# alu.net
KiCad netlist of a schematic drawn in EAGLE
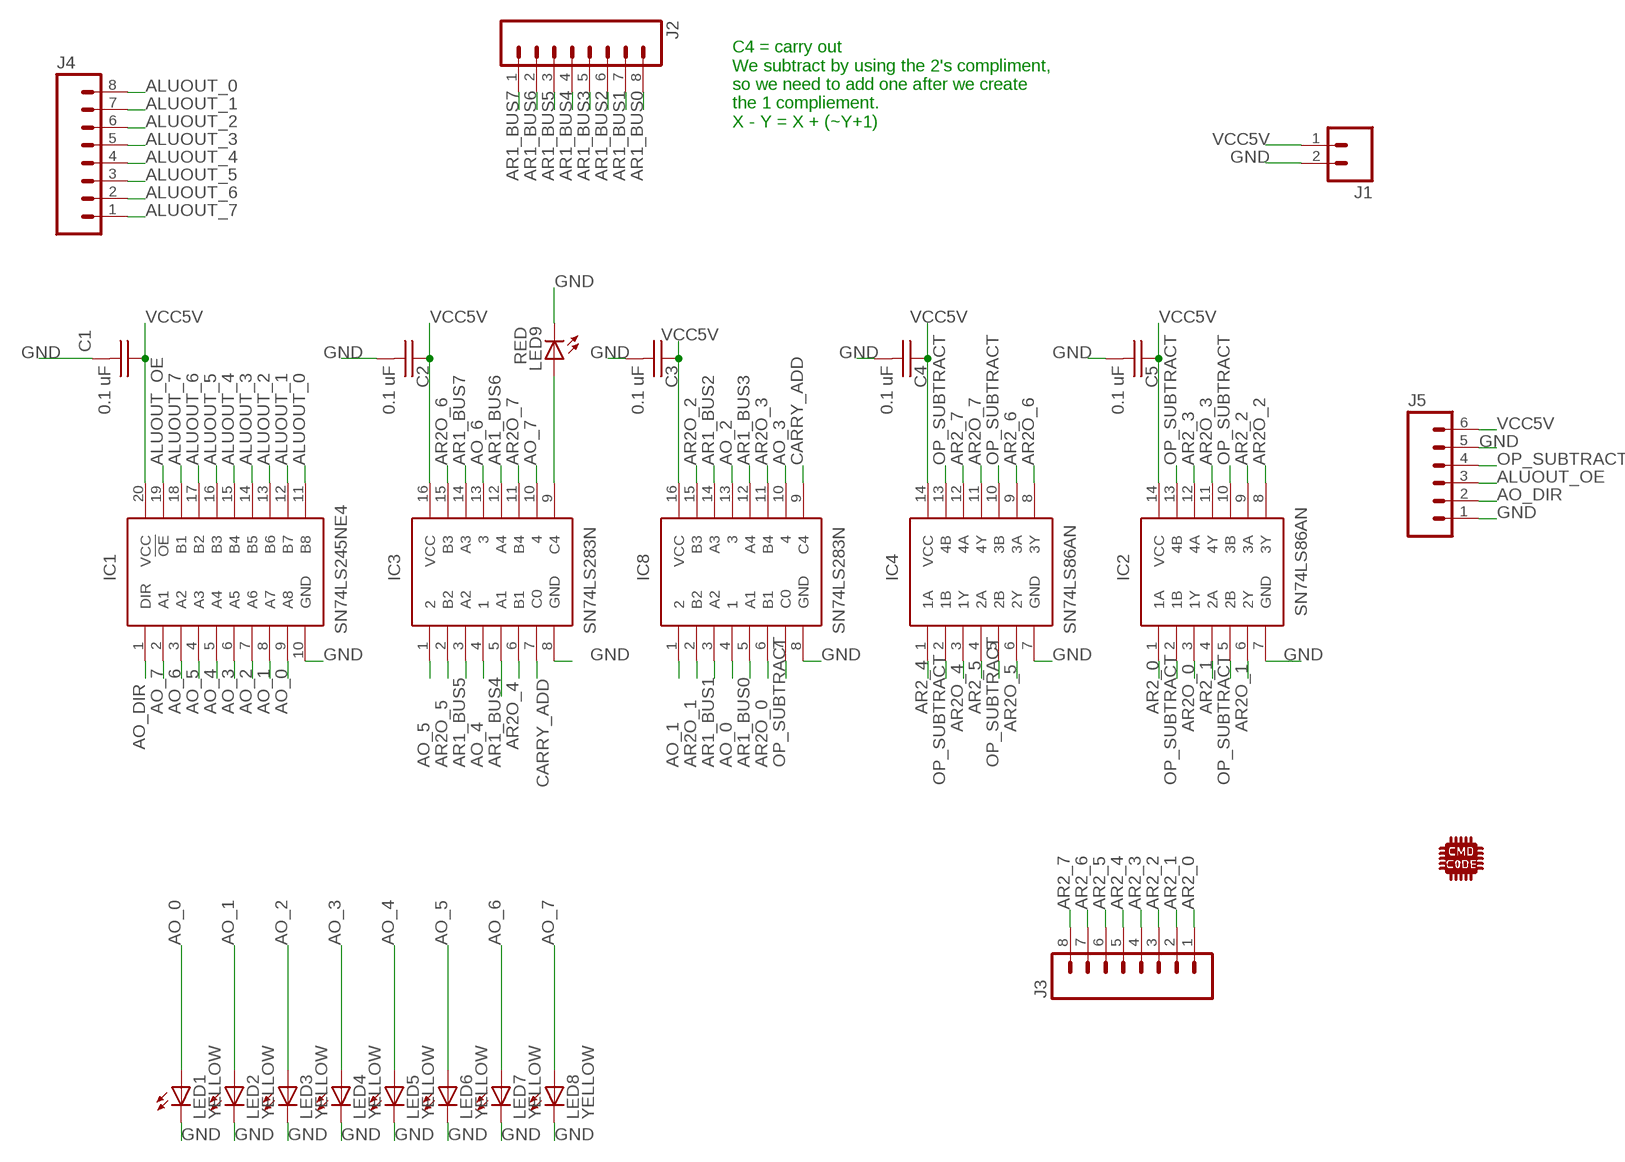
[diagram p0: schematic, sheet 1]

(export (version "E")
  (design (tool "Eeschema 10.0.6"))
  (components
    (comp (ref "C1")
      (value "0.1 uF")
      (footprint "eagle-import:C050-025X075")
      (libsource (lib "eagle-import") (part "C-US050-025X075"))
    )
    (comp (ref "C2")
      (value "0.1 uF")
      (footprint "eagle-import:C050-025X075")
      (libsource (lib "eagle-import") (part "C-US050-025X075"))
    )
    (comp (ref "C3")
      (value "0.1 uF")
      (footprint "eagle-import:C050-025X075")
      (libsource (lib "eagle-import") (part "C-US050-025X075"))
    )
    (comp (ref "C4")
      (value "0.1 uF")
      (footprint "eagle-import:C050-025X075")
      (libsource (lib "eagle-import") (part "C-US050-025X075"))
    )
    (comp (ref "C5")
      (value "0.1 uF")
      (footprint "eagle-import:C050-025X075")
      (libsource (lib "eagle-import") (part "C-US050-025X075"))
    )
    (comp (ref "IC1")
      (value "SN74LS245NE4")
      (footprint "eagle-import:DIP794W53P254L2540H508Q20N")
      (fields (field (name "MOUSER_PART_NUMBER") "595-SN74LS245NE4"))
      (libsource (lib "eagle-import") (part "SN74LS245NE4"))
    )
    (comp (ref "IC2")
      (value "SN74LS86AN")
      (footprint "eagle-import:DIP254P762X508-14")
      (fields (field (name "MOUSER_PART_NUMBER") "595-SN74LS86AN") (field (name "RS_PART_NUMBER") "3686641"))
      (libsource (lib "eagle-import") (part "SN74LS86AN"))
    )
    (comp (ref "IC3")
      (value "SN74LS283N")
      (footprint "eagle-import:DIP254P762X508-16")
      (fields (field (name "MOUSER_PART_NUMBER") "595-SN74LS283N") (field (name "RS_PART_NUMBER") "0309212"))
      (libsource (lib "eagle-import") (part "SN74LS283N"))
    )
    (comp (ref "IC4")
      (value "SN74LS86AN")
      (footprint "eagle-import:DIP254P762X508-14")
      (fields (field (name "MOUSER_PART_NUMBER") "595-SN74LS86AN") (field (name "RS_PART_NUMBER") "3686641"))
      (libsource (lib "eagle-import") (part "SN74LS86AN"))
    )
    (comp (ref "IC8")
      (value "SN74LS283N")
      (footprint "eagle-import:DIP254P762X508-16")
      (fields (field (name "MOUSER_PART_NUMBER") "595-SN74LS283N") (field (name "RS_PART_NUMBER") "0309212"))
      (libsource (lib "eagle-import") (part "SN74LS283N"))
    )
    (comp (ref "J1")
      (value "M02PTH")
      (footprint "eagle-import:1X02")
      (libsource (lib "eagle-import") (part "M02PTH"))
    )
    (comp (ref "J2")
      (value "M08SILK_FEMALE_PTH")
      (footprint "eagle-import:1X08")
      (libsource (lib "eagle-import") (part "M08SILK_FEMALE_PTH"))
    )
    (comp (ref "J3")
      (value "M08SILK_FEMALE_PTH")
      (footprint "eagle-import:1X08")
      (libsource (lib "eagle-import") (part "M08SILK_FEMALE_PTH"))
    )
    (comp (ref "J4")
      (value "M08SILK_FEMALE_PTH")
      (footprint "eagle-import:1X08")
      (libsource (lib "eagle-import") (part "M08SILK_FEMALE_PTH"))
    )
    (comp (ref "J5")
      (value "M06SILK_FEMALE_PTH")
      (footprint "eagle-import:1X06")
      (libsource (lib "eagle-import") (part "M06SILK_FEMALE_PTH"))
    )
    (comp (ref "LED1")
      (value "YELLOW")
      (footprint "eagle-import:LED3MM-NS")
      (libsource (lib "eagle-import") (part "LED-3MM-NO_SILK"))
    )
    (comp (ref "LED2")
      (value "YELLOW")
      (footprint "eagle-import:LED3MM-NS")
      (libsource (lib "eagle-import") (part "LED-3MM-NO_SILK"))
    )
    (comp (ref "LED3")
      (value "YELLOW")
      (footprint "eagle-import:LED3MM-NS")
      (libsource (lib "eagle-import") (part "LED-3MM-NO_SILK"))
    )
    (comp (ref "LED4")
      (value "YELLOW")
      (footprint "eagle-import:LED3MM-NS")
      (libsource (lib "eagle-import") (part "LED-3MM-NO_SILK"))
    )
    (comp (ref "LED5")
      (value "YELLOW")
      (footprint "eagle-import:LED3MM-NS")
      (libsource (lib "eagle-import") (part "LED-3MM-NO_SILK"))
    )
    (comp (ref "LED6")
      (value "YELLOW")
      (footprint "eagle-import:LED3MM-NS")
      (libsource (lib "eagle-import") (part "LED-3MM-NO_SILK"))
    )
    (comp (ref "LED7")
      (value "YELLOW")
      (footprint "eagle-import:LED3MM-NS")
      (libsource (lib "eagle-import") (part "LED-3MM-NO_SILK"))
    )
    (comp (ref "LED8")
      (value "YELLOW")
      (footprint "eagle-import:LED3MM-NS")
      (libsource (lib "eagle-import") (part "LED-3MM-NO_SILK"))
    )
    (comp (ref "LED9")
      (value "RED")
      (footprint "eagle-import:LED3MM-NS")
      (libsource (lib "eagle-import") (part "LED-3MM-NO_SILK"))
    )
    (comp (ref "U$1")
      (value "CMD_C0DE_LOGOCMD_CODE_LOGO_TOP_COPPER")
      (footprint "eagle-import:CMD_C0DE_LOGO_TOP_COPPER")
      (libsource (lib "eagle-import") (part "CMD_C0DE_LOGOCMD_CODE_LOGO_TOP_COPPER"))
    )
  )
  (nets
    (net (code "1") (name "/ALUOUT_0") (class "Default")
      (node (ref "IC1") (pin "11") (pinfunction "B8_11") (pintype "bidirectional"))
      (node (ref "J4") (pin "8") (pinfunction "8_8") (pintype "passive"))
    )
    (net (code "2") (name "/ALUOUT_1") (class "Default")
      (node (ref "IC1") (pin "12") (pinfunction "B7_12") (pintype "bidirectional"))
      (node (ref "J4") (pin "7") (pinfunction "7_7") (pintype "passive"))
    )
    (net (code "3") (name "/ALUOUT_2") (class "Default")
      (node (ref "IC1") (pin "13") (pinfunction "B6_13") (pintype "bidirectional"))
      (node (ref "J4") (pin "6") (pinfunction "6_6") (pintype "passive"))
    )
    (net (code "4") (name "/ALUOUT_3") (class "Default")
      (node (ref "IC1") (pin "14") (pinfunction "B5_14") (pintype "bidirectional"))
      (node (ref "J4") (pin "5") (pinfunction "5_5") (pintype "passive"))
    )
    (net (code "5") (name "/ALUOUT_4") (class "Default")
      (node (ref "IC1") (pin "15") (pinfunction "B4_15") (pintype "bidirectional"))
      (node (ref "J4") (pin "4") (pinfunction "4_4") (pintype "passive"))
    )
    (net (code "6") (name "/ALUOUT_5") (class "Default")
      (node (ref "IC1") (pin "16") (pinfunction "B3_16") (pintype "bidirectional"))
      (node (ref "J4") (pin "3") (pinfunction "3_3") (pintype "passive"))
    )
    (net (code "7") (name "/ALUOUT_6") (class "Default")
      (node (ref "IC1") (pin "17") (pinfunction "B2_17") (pintype "bidirectional"))
      (node (ref "J4") (pin "2") (pinfunction "2_2") (pintype "passive"))
    )
    (net (code "8") (name "/ALUOUT_7") (class "Default")
      (node (ref "IC1") (pin "18") (pinfunction "B1_18") (pintype "bidirectional"))
      (node (ref "J4") (pin "1") (pinfunction "1_1") (pintype "passive"))
    )
    (net (code "9") (name "/ALUOUT_OE") (class "Default")
      (node (ref "IC1") (pin "19") (pinfunction "~{OE}_19") (pintype "bidirectional"))
      (node (ref "J5") (pin "3") (pinfunction "3_3") (pintype "passive"))
    )
    (net (code "10") (name "/AO_0") (class "Default")
      (node (ref "IC1") (pin "9") (pinfunction "A8_9") (pintype "bidirectional"))
      (node (ref "IC8") (pin "4") (pinfunction "1_4") (pintype "bidirectional"))
      (node (ref "LED1") (pin "A") (pinfunction "A_A") (pintype "input"))
    )
    (net (code "11") (name "/AO_1") (class "Default")
      (node (ref "IC1") (pin "8") (pinfunction "A7_8") (pintype "bidirectional"))
      (node (ref "IC8") (pin "1") (pinfunction "2_1") (pintype "bidirectional"))
      (node (ref "LED2") (pin "A") (pinfunction "A_A") (pintype "input"))
    )
    (net (code "12") (name "/AO_2") (class "Default")
      (node (ref "IC1") (pin "7") (pinfunction "A6_7") (pintype "bidirectional"))
      (node (ref "IC8") (pin "13") (pinfunction "3_13") (pintype "bidirectional"))
      (node (ref "LED3") (pin "A") (pinfunction "A_A") (pintype "input"))
    )
    (net (code "13") (name "/AO_3") (class "Default")
      (node (ref "IC1") (pin "6") (pinfunction "A5_6") (pintype "bidirectional"))
      (node (ref "IC8") (pin "10") (pinfunction "4_10") (pintype "bidirectional"))
      (node (ref "LED4") (pin "A") (pinfunction "A_A") (pintype "input"))
    )
    (net (code "14") (name "/AO_4") (class "Default")
      (node (ref "IC1") (pin "5") (pinfunction "A4_5") (pintype "bidirectional"))
      (node (ref "IC3") (pin "4") (pinfunction "1_4") (pintype "bidirectional"))
      (node (ref "LED5") (pin "A") (pinfunction "A_A") (pintype "input"))
    )
    (net (code "15") (name "/AO_5") (class "Default")
      (node (ref "IC1") (pin "4") (pinfunction "A3_4") (pintype "bidirectional"))
      (node (ref "IC3") (pin "1") (pinfunction "2_1") (pintype "bidirectional"))
      (node (ref "LED6") (pin "A") (pinfunction "A_A") (pintype "input"))
    )
    (net (code "16") (name "/AO_6") (class "Default")
      (node (ref "IC1") (pin "3") (pinfunction "A2_3") (pintype "bidirectional"))
      (node (ref "IC3") (pin "13") (pinfunction "3_13") (pintype "bidirectional"))
      (node (ref "LED7") (pin "A") (pinfunction "A_A") (pintype "input"))
    )
    (net (code "17") (name "/AO_7") (class "Default")
      (node (ref "IC1") (pin "2") (pinfunction "A1_2") (pintype "bidirectional"))
      (node (ref "IC3") (pin "10") (pinfunction "4_10") (pintype "bidirectional"))
      (node (ref "LED8") (pin "A") (pinfunction "A_A") (pintype "input"))
    )
    (net (code "18") (name "/AO_DIR") (class "Default")
      (node (ref "IC1") (pin "1") (pinfunction "DIR_1") (pintype "bidirectional"))
      (node (ref "J5") (pin "2") (pinfunction "2_2") (pintype "passive"))
    )
    (net (code "19") (name "/AR1_BUS0") (class "Default")
      (node (ref "IC8") (pin "5") (pinfunction "A1_5") (pintype "bidirectional"))
      (node (ref "J2") (pin "8") (pinfunction "8_8") (pintype "passive"))
    )
    (net (code "20") (name "/AR1_BUS1") (class "Default")
      (node (ref "IC8") (pin "3") (pinfunction "A2_3") (pintype "bidirectional"))
      (node (ref "J2") (pin "7") (pinfunction "7_7") (pintype "passive"))
    )
    (net (code "21") (name "/AR1_BUS2") (class "Default")
      (node (ref "IC8") (pin "14") (pinfunction "A3_14") (pintype "bidirectional"))
      (node (ref "J2") (pin "6") (pinfunction "6_6") (pintype "passive"))
    )
    (net (code "22") (name "/AR1_BUS3") (class "Default")
      (node (ref "IC8") (pin "12") (pinfunction "A4_12") (pintype "bidirectional"))
      (node (ref "J2") (pin "5") (pinfunction "5_5") (pintype "passive"))
    )
    (net (code "23") (name "/AR1_BUS4") (class "Default")
      (node (ref "IC3") (pin "5") (pinfunction "A1_5") (pintype "bidirectional"))
      (node (ref "J2") (pin "4") (pinfunction "4_4") (pintype "passive"))
    )
    (net (code "24") (name "/AR1_BUS5") (class "Default")
      (node (ref "IC3") (pin "3") (pinfunction "A2_3") (pintype "bidirectional"))
      (node (ref "J2") (pin "3") (pinfunction "3_3") (pintype "passive"))
    )
    (net (code "25") (name "/AR1_BUS6") (class "Default")
      (node (ref "IC3") (pin "12") (pinfunction "A4_12") (pintype "bidirectional"))
      (node (ref "J2") (pin "2") (pinfunction "2_2") (pintype "passive"))
    )
    (net (code "26") (name "/AR1_BUS7") (class "Default")
      (node (ref "IC3") (pin "14") (pinfunction "A3_14") (pintype "bidirectional"))
      (node (ref "J2") (pin "1") (pinfunction "1_1") (pintype "passive"))
    )
    (net (code "27") (name "/AR2O_0") (class "Default")
      (node (ref "IC2") (pin "3") (pinfunction "1Y_3") (pintype "bidirectional"))
      (node (ref "IC8") (pin "6") (pinfunction "B1_6") (pintype "bidirectional"))
    )
    (net (code "28") (name "/AR2O_1") (class "Default")
      (node (ref "IC2") (pin "6") (pinfunction "2Y_6") (pintype "bidirectional"))
      (node (ref "IC8") (pin "2") (pinfunction "B2_2") (pintype "bidirectional"))
    )
    (net (code "29") (name "/AR2O_2") (class "Default")
      (node (ref "IC2") (pin "8") (pinfunction "3Y_8") (pintype "bidirectional"))
      (node (ref "IC8") (pin "15") (pinfunction "B3_15") (pintype "bidirectional"))
    )
    (net (code "30") (name "/AR2O_3") (class "Default")
      (node (ref "IC2") (pin "11") (pinfunction "4Y_11") (pintype "bidirectional"))
      (node (ref "IC8") (pin "11") (pinfunction "B4_11") (pintype "bidirectional"))
    )
    (net (code "31") (name "/AR2O_4") (class "Default")
      (node (ref "IC3") (pin "6") (pinfunction "B1_6") (pintype "bidirectional"))
      (node (ref "IC4") (pin "3") (pinfunction "1Y_3") (pintype "bidirectional"))
    )
    (net (code "32") (name "/AR2O_5") (class "Default")
      (node (ref "IC3") (pin "2") (pinfunction "B2_2") (pintype "bidirectional"))
      (node (ref "IC4") (pin "6") (pinfunction "2Y_6") (pintype "bidirectional"))
    )
    (net (code "33") (name "/AR2O_6") (class "Default")
      (node (ref "IC3") (pin "15") (pinfunction "B3_15") (pintype "bidirectional"))
      (node (ref "IC4") (pin "8") (pinfunction "3Y_8") (pintype "bidirectional"))
    )
    (net (code "34") (name "/AR2O_7") (class "Default")
      (node (ref "IC3") (pin "11") (pinfunction "B4_11") (pintype "bidirectional"))
      (node (ref "IC4") (pin "11") (pinfunction "4Y_11") (pintype "bidirectional"))
    )
    (net (code "35") (name "/AR2_0") (class "Default")
      (node (ref "IC2") (pin "1") (pinfunction "1A_1") (pintype "bidirectional"))
      (node (ref "J3") (pin "1") (pinfunction "1_1") (pintype "passive"))
    )
    (net (code "36") (name "/AR2_1") (class "Default")
      (node (ref "IC2") (pin "4") (pinfunction "2A_4") (pintype "bidirectional"))
      (node (ref "J3") (pin "2") (pinfunction "2_2") (pintype "passive"))
    )
    (net (code "37") (name "/AR2_2") (class "Default")
      (node (ref "IC2") (pin "9") (pinfunction "3A_9") (pintype "bidirectional"))
      (node (ref "J3") (pin "3") (pinfunction "3_3") (pintype "passive"))
    )
    (net (code "38") (name "/AR2_3") (class "Default")
      (node (ref "IC2") (pin "12") (pinfunction "4A_12") (pintype "bidirectional"))
      (node (ref "J3") (pin "4") (pinfunction "4_4") (pintype "passive"))
    )
    (net (code "39") (name "/AR2_4") (class "Default")
      (node (ref "IC4") (pin "1") (pinfunction "1A_1") (pintype "bidirectional"))
      (node (ref "J3") (pin "5") (pinfunction "5_5") (pintype "passive"))
    )
    (net (code "40") (name "/AR2_5") (class "Default")
      (node (ref "IC4") (pin "4") (pinfunction "2A_4") (pintype "bidirectional"))
      (node (ref "J3") (pin "6") (pinfunction "6_6") (pintype "passive"))
    )
    (net (code "41") (name "/AR2_6") (class "Default")
      (node (ref "IC4") (pin "9") (pinfunction "3A_9") (pintype "bidirectional"))
      (node (ref "J3") (pin "7") (pinfunction "7_7") (pintype "passive"))
    )
    (net (code "42") (name "/AR2_7") (class "Default")
      (node (ref "IC4") (pin "12") (pinfunction "4A_12") (pintype "bidirectional"))
      (node (ref "J3") (pin "8") (pinfunction "8_8") (pintype "passive"))
    )
    (net (code "43") (name "/CARRY_ADD") (class "Default")
      (node (ref "IC3") (pin "7") (pinfunction "C0_7") (pintype "bidirectional"))
      (node (ref "IC8") (pin "9") (pinfunction "C4_9") (pintype "bidirectional"))
    )
    (net (code "44") (name "/GND") (class "Default")
      (node (ref "C1") (pin "2") (pinfunction "2_2") (pintype "passive"))
      (node (ref "C2") (pin "2") (pinfunction "2_2") (pintype "passive"))
      (node (ref "C3") (pin "2") (pinfunction "2_2") (pintype "passive"))
      (node (ref "C4") (pin "2") (pinfunction "2_2") (pintype "passive"))
      (node (ref "C5") (pin "2") (pinfunction "2_2") (pintype "passive"))
      (node (ref "IC1") (pin "10") (pinfunction "GND_10") (pintype "bidirectional"))
      (node (ref "IC2") (pin "7") (pinfunction "GND_7") (pintype "bidirectional"))
      (node (ref "IC3") (pin "8") (pinfunction "GND_8") (pintype "bidirectional"))
      (node (ref "IC4") (pin "7") (pinfunction "GND_7") (pintype "bidirectional"))
      (node (ref "IC8") (pin "8") (pinfunction "GND_8") (pintype "bidirectional"))
      (node (ref "J1") (pin "2") (pinfunction "2_2") (pintype "passive"))
      (node (ref "J5") (pin "1") (pinfunction "1_1") (pintype "passive"))
      (node (ref "J5") (pin "5") (pinfunction "5_5") (pintype "passive"))
      (node (ref "LED1") (pin "K") (pinfunction "C_K") (pintype "output"))
      (node (ref "LED2") (pin "K") (pinfunction "C_K") (pintype "output"))
      (node (ref "LED3") (pin "K") (pinfunction "C_K") (pintype "output"))
      (node (ref "LED4") (pin "K") (pinfunction "C_K") (pintype "output"))
      (node (ref "LED5") (pin "K") (pinfunction "C_K") (pintype "output"))
      (node (ref "LED6") (pin "K") (pinfunction "C_K") (pintype "output"))
      (node (ref "LED7") (pin "K") (pinfunction "C_K") (pintype "output"))
      (node (ref "LED8") (pin "K") (pinfunction "C_K") (pintype "output"))
      (node (ref "LED9") (pin "K") (pinfunction "C_K") (pintype "output"))
    )
    (net (code "45") (name "/OP_SUBTRACT") (class "Default")
      (node (ref "IC2") (pin "10") (pinfunction "3B_10") (pintype "bidirectional"))
      (node (ref "IC2") (pin "13") (pinfunction "4B_13") (pintype "bidirectional"))
      (node (ref "IC2") (pin "2") (pinfunction "1B_2") (pintype "bidirectional"))
      (node (ref "IC2") (pin "5") (pinfunction "2B_5") (pintype "bidirectional"))
      (node (ref "IC4") (pin "10") (pinfunction "3B_10") (pintype "bidirectional"))
      (node (ref "IC4") (pin "13") (pinfunction "4B_13") (pintype "bidirectional"))
      (node (ref "IC4") (pin "2") (pinfunction "1B_2") (pintype "bidirectional"))
      (node (ref "IC4") (pin "5") (pinfunction "2B_5") (pintype "bidirectional"))
      (node (ref "IC8") (pin "7") (pinfunction "C0_7") (pintype "bidirectional"))
      (node (ref "J5") (pin "4") (pinfunction "4_4") (pintype "passive"))
    )
    (net (code "46") (name "/VCC5V") (class "Default")
      (node (ref "C1") (pin "1") (pinfunction "1_1") (pintype "passive"))
      (node (ref "C2") (pin "1") (pinfunction "1_1") (pintype "passive"))
      (node (ref "C3") (pin "1") (pinfunction "1_1") (pintype "passive"))
      (node (ref "C4") (pin "1") (pinfunction "1_1") (pintype "passive"))
      (node (ref "C5") (pin "1") (pinfunction "1_1") (pintype "passive"))
      (node (ref "IC1") (pin "20") (pinfunction "VCC_20") (pintype "bidirectional"))
      (node (ref "IC2") (pin "14") (pinfunction "VCC_14") (pintype "bidirectional"))
      (node (ref "IC3") (pin "16") (pinfunction "VCC_16") (pintype "bidirectional"))
      (node (ref "IC4") (pin "14") (pinfunction "VCC_14") (pintype "bidirectional"))
      (node (ref "IC8") (pin "16") (pinfunction "VCC_16") (pintype "bidirectional"))
      (node (ref "J1") (pin "1") (pinfunction "1_1") (pintype "passive"))
      (node (ref "J5") (pin "6") (pinfunction "6_6") (pintype "passive"))
    )
    (net (code "47") (name "Net-(IC3-C4)") (class "Default")
      (node (ref "IC3") (pin "9") (pinfunction "C4_9") (pintype "bidirectional"))
      (node (ref "LED9") (pin "A") (pinfunction "A_A") (pintype "input"))
    )
  )
)
